# Float_Receiver_PCB.net
KiCad netlist of a schematic drawn in Altium Designer
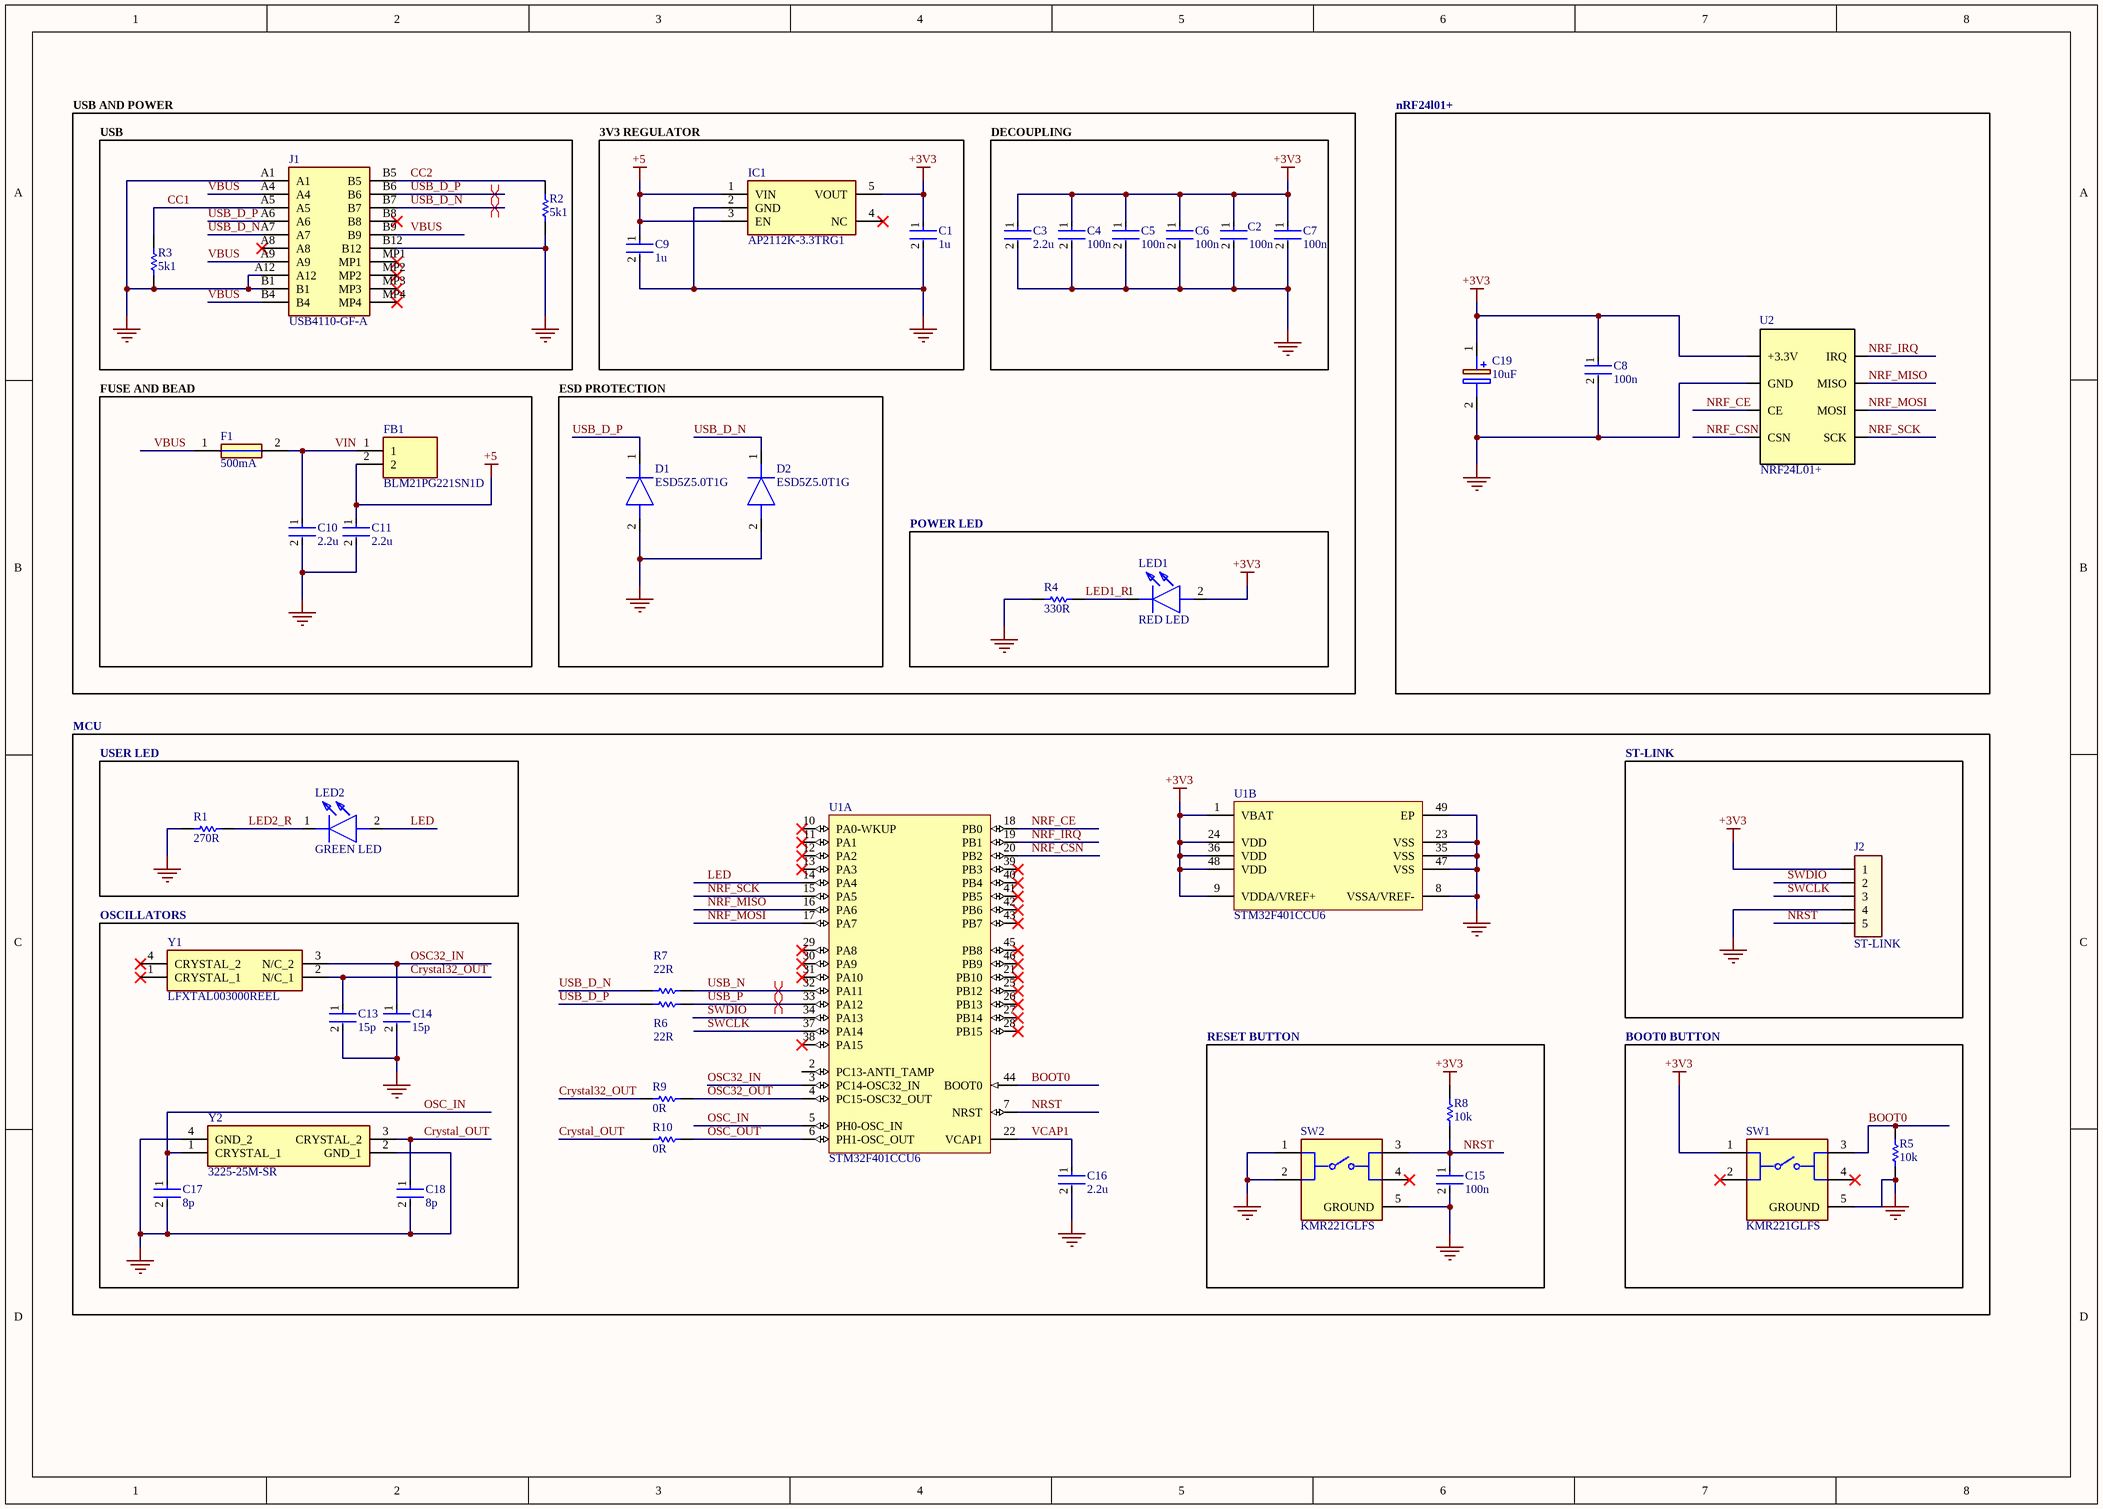
[diagram p0: Float_Receiver_PCB.SchDoc]

(export (version "E")
  (design (tool "Eeschema 10.0.6"))
  (components
    (comp (ref "C1")
      (value "1u")
      (footprint "FP-0805-L_2_01_0_2-W_1_25-MFG")
      (fields (field (name "TOLERANCE") "10%") (field (name "VOLTAGE") "10V"))
      (libsource (lib "Altium Content Vault") (part "b4654b650e69147ec39a6b967a45e02"))
    )
    (comp (ref "C2")
      (value "100n")
      (footprint "FP-0805-L_2_01_0_2-W_1_25-MFG")
      (fields (field (name "TOLERANCE") "10%") (field (name "VOLTAGE") "10V"))
      (libsource (lib "Altium Content Vault") (part "b4654b650e69147ec39a6b967a45e02"))
    )
    (comp (ref "C3")
      (value "2.2u")
      (footprint "FP-0805-L_2_01_0_2-W_1_25-MFG")
      (fields (field (name "TOLERANCE") "10%") (field (name "VOLTAGE") "10V"))
      (libsource (lib "Altium Content Vault") (part "b4654b650e69147ec39a6b967a45e02"))
    )
    (comp (ref "C4")
      (value "100n")
      (footprint "FP-0805-L_2_01_0_2-W_1_25-MFG")
      (fields (field (name "TOLERANCE") "10%") (field (name "VOLTAGE") "10V"))
      (libsource (lib "Altium Content Vault") (part "b4654b650e69147ec39a6b967a45e02"))
    )
    (comp (ref "C5")
      (value "100n")
      (footprint "FP-0805-L_2_01_0_2-W_1_25-MFG")
      (fields (field (name "TOLERANCE") "10%") (field (name "VOLTAGE") "10V"))
      (libsource (lib "Altium Content Vault") (part "b4654b650e69147ec39a6b967a45e02"))
    )
    (comp (ref "C6")
      (value "100n")
      (footprint "FP-0805-L_2_01_0_2-W_1_25-MFG")
      (fields (field (name "TOLERANCE") "10%") (field (name "VOLTAGE") "10V"))
      (libsource (lib "Altium Content Vault") (part "b4654b650e69147ec39a6b967a45e02"))
    )
    (comp (ref "C7")
      (value "100n")
      (footprint "FP-0805-L_2_01_0_2-W_1_25-MFG")
      (fields (field (name "TOLERANCE") "10%") (field (name "VOLTAGE") "10V"))
      (libsource (lib "Altium Content Vault") (part "b4654b650e69147ec39a6b967a45e02"))
    )
    (comp (ref "C8")
      (value "100n")
      (footprint "FP-0805-L_2_01_0_2-W_1_25-MFG")
      (fields (field (name "TOLERANCE") "10%") (field (name "VOLTAGE") "10V"))
      (libsource (lib "Altium Content Vault") (part "b4654b650e69147ec39a6b967a45e02"))
    )
    (comp (ref "C9")
      (value "1u")
      (footprint "FP-0805-L_2_01_0_2-W_1_25-MFG")
      (fields (field (name "TOLERANCE") "10%") (field (name "VOLTAGE") "10V"))
      (libsource (lib "Altium Content Vault") (part "b4654b650e69147ec39a6b967a45e02"))
    )
    (comp (ref "C10")
      (value "2.2u")
      (footprint "FP-0805-L_2_01_0_2-W_1_25-MFG")
      (fields (field (name "TOLERANCE") "10%") (field (name "VOLTAGE") "10V"))
      (libsource (lib "Altium Content Vault") (part "b4654b650e69147ec39a6b967a45e02"))
    )
    (comp (ref "C11")
      (value "2.2u")
      (footprint "FP-0805-L_2_01_0_2-W_1_25-MFG")
      (fields (field (name "TOLERANCE") "10%") (field (name "VOLTAGE") "10V"))
      (libsource (lib "Altium Content Vault") (part "b4654b650e69147ec39a6b967a45e02"))
    )
    (comp (ref "C13")
      (value "15p")
      (footprint "FP-0805-L_2_01_0_2-W_1_25-MFG")
      (fields (field (name "TOLERANCE") "10%") (field (name "VOLTAGE") "10V"))
      (libsource (lib "Altium Content Vault") (part "b4654b650e69147ec39a6b967a45e02"))
    )
    (comp (ref "C14")
      (value "15p")
      (footprint "FP-0805-L_2_01_0_2-W_1_25-MFG")
      (fields (field (name "TOLERANCE") "10%") (field (name "VOLTAGE") "10V"))
      (libsource (lib "Altium Content Vault") (part "b4654b650e69147ec39a6b967a45e02"))
    )
    (comp (ref "C15")
      (value "100n")
      (footprint "FP-0805-L_2_01_0_2-W_1_25-MFG")
      (fields (field (name "TOLERANCE") "10%") (field (name "VOLTAGE") "10V"))
      (libsource (lib "Altium Content Vault") (part "b4654b650e69147ec39a6b967a45e02"))
    )
    (comp (ref "C16")
      (value "2.2u")
      (footprint "FP-0805-L_2_01_0_2-W_1_25-MFG")
      (fields (field (name "TOLERANCE") "10%") (field (name "VOLTAGE") "10V"))
      (libsource (lib "Altium Content Vault") (part "b4654b650e69147ec39a6b967a45e02"))
    )
    (comp (ref "C17")
      (value "8p")
      (footprint "FP-0805-L_2_01_0_2-W_1_25-MFG")
      (fields (field (name "TOLERANCE") "10%") (field (name "VOLTAGE") "10V"))
      (libsource (lib "Altium Content Vault") (part "b4654b650e69147ec39a6b967a45e02"))
    )
    (comp (ref "C18")
      (value "8p")
      (footprint "FP-0805-L_2_01_0_2-W_1_25-MFG")
      (fields (field (name "TOLERANCE") "10%") (field (name "VOLTAGE") "10V"))
      (libsource (lib "Altium Content Vault") (part "b4654b650e69147ec39a6b967a45e02"))
    )
    (comp (ref "C19")
      (value "10uF")
      (footprint "SamacSys:EEE1AA220WR")
      (description "Capacitor Polarised")
      (fields (field (name "MANUFACTURER_PART_NUMBER") "EEE1CA100SR"))
      (libsource (lib "*") (part "EEE1CA100SR"))
    )
    (comp (ref "D1")
      (value "ESD5Z5.0T1G")
      (footprint "SamacSys:SODFL1608X70N")
      (description "Diode")
      (fields (field (name "MOUSER PART NUMBER") "863-ESD5Z5.0T1G"))
      (libsource (lib "*") (part "ESD5Z5.0T1G"))
    )
    (comp (ref "D2")
      (value "ESD5Z5.0T1G")
      (footprint "SamacSys:SODFL1608X70N")
      (description "Diode")
      (fields (field (name "MOUSER PART NUMBER") "863-ESD5Z5.0T1G"))
      (libsource (lib "*") (part "ESD5Z5.0T1G"))
    )
    (comp (ref "F1")
      (value "500mA")
      (footprint "SamacSys:FUSC3216X75N")
      (description "Fuse")
      (fields (field (name "MANUFACTURER_PART_NUMBER") "0ZCJ0025FF2E"))
      (libsource (lib "*") (part "0ZCJ0025FF2E"))
    )
    (comp (ref "FB1")
      (value "BLM21PG221SN1D")
      (footprint "SamacSys:BEADC2012X105N")
      (description "Ferrite Bead")
      (fields (field (name "MOUSER PART NUMBER") "81-BLM21P221SG"))
      (libsource (lib "*") (part "BLM21PG221SN1D"))
    )
    (comp (ref "IC1")
      (value "AP2112K-3.3TRG1")
      (footprint "SamacSys:SOT95P285X140-5N")
      (description "Integrated Circuit")
      (fields (field (name "MOUSER PART NUMBER") "621-AP2112K-3.3TRG1"))
      (libsource (lib "*") (part "AP2112K-3.3TRG1"))
    )
    (comp (ref "J1")
      (value "USB4110-GF-A")
      (footprint "SamacSys:USB4110GFA")
      (description "Connector")
      (fields (field (name "MOUSER PART NUMBER") "640-USB4110-GF-A"))
      (libsource (lib "*") (part "USB4110-GF-A"))
    )
    (comp (ref "J2")
      (value "ST-LINK")
      (footprint "goldpin:goldpin5")
      (libsource (lib "goldpin") (part "goldpin_5"))
    )
    (comp (ref "LED1")
      (value "RED LED")
      (footprint "SamacSys:LEDC2012X80N")
      (description "LED")
      (fields
        (field (name "MANUFACTURER_PART_NUMBER") "HSMG-C170")
        (field (name "MOUSER PART NUMBER") "630-HSMG-C170")
      )
      (libsource (lib "*") (part "HSMG-C170"))
    )
    (comp (ref "LED2")
      (value "GREEN LED")
      (footprint "SamacSys:LEDC2012X80N")
      (description "LED")
      (fields
        (field (name "MANUFACTURER_PART_NUMBER") "HSMG-C170")
        (field (name "MOUSER PART NUMBER") "630-HSMG-C170")
      )
      (libsource (lib "*") (part "HSMG-C170"))
    )
    (comp (ref "R1")
      (value "270R")
      (footprint "RESC2013X60X35ML10T20")
      (fields (field (name "TOLERANCE") "1%") (field (name "MANUFACTURER") "Yageo"))
      (libsource (lib "Altium Content Vault") (part "RES-2"))
    )
    (comp (ref "R2")
      (value "5k1")
      (footprint "RESC2013X60X35ML10T20")
      (fields (field (name "TOLERANCE") "1%") (field (name "MANUFACTURER") "Yageo"))
      (libsource (lib "Altium Content Vault") (part "RES-2"))
    )
    (comp (ref "R3")
      (value "5k1")
      (footprint "RESC2013X60X35ML10T20")
      (fields (field (name "TOLERANCE") "1%") (field (name "MANUFACTURER") "Yageo"))
      (libsource (lib "Altium Content Vault") (part "RES-2"))
    )
    (comp (ref "R4")
      (value "330R")
      (footprint "RESC2013X60X35ML10T20")
      (fields (field (name "TOLERANCE") "1%") (field (name "MANUFACTURER") "Yageo"))
      (libsource (lib "Altium Content Vault") (part "RES-2"))
    )
    (comp (ref "R5")
      (value "10k")
      (footprint "RESC2013X60X35ML10T20")
      (fields (field (name "TOLERANCE") "1%") (field (name "MANUFACTURER") "Yageo"))
      (libsource (lib "Altium Content Vault") (part "RES-2"))
    )
    (comp (ref "R6")
      (value "22R")
      (footprint "RESC2013X60X35ML10T20")
      (fields (field (name "TOLERANCE") "1%") (field (name "MANUFACTURER") "Yageo"))
      (libsource (lib "Altium Content Vault") (part "RES-2"))
    )
    (comp (ref "R7")
      (value "22R")
      (footprint "RESC2013X60X35ML10T20")
      (fields (field (name "TOLERANCE") "1%") (field (name "MANUFACTURER") "Yageo"))
      (libsource (lib "Altium Content Vault") (part "RES-2"))
    )
    (comp (ref "R8")
      (value "10k")
      (footprint "RESC2013X60X35ML10T20")
      (fields (field (name "TOLERANCE") "1%") (field (name "MANUFACTURER") "Yageo"))
      (libsource (lib "Altium Content Vault") (part "RES-2"))
    )
    (comp (ref "R9")
      (value "0R")
      (footprint "RESC2013X60X35ML10T20")
      (fields (field (name "TOLERANCE") "1%") (field (name "MANUFACTURER") "Yageo"))
      (libsource (lib "Altium Content Vault") (part "RES-2"))
    )
    (comp (ref "R10")
      (value "0R")
      (footprint "RESC2013X60X35ML10T20")
      (fields (field (name "TOLERANCE") "1%") (field (name "MANUFACTURER") "Yageo"))
      (libsource (lib "Altium Content Vault") (part "RES-2"))
    )
    (comp (ref "SW1")
      (value "KMR221GLFS")
      (footprint "FP-KMR221GLFS-MFG")
      (description "SWITCH TACTILE SPST-NO 0.05A 32V")
      (libsource (lib "Altium Content Vault") (part "067e1cfe0b8977aedbfee7786663f4c"))
    )
    (comp (ref "SW2")
      (value "KMR221GLFS")
      (footprint "FP-KMR221GLFS-MFG")
      (description "SWITCH TACTILE SPST-NO 0.05A 32V")
      (libsource (lib "Altium Content Vault") (part "067e1cfe0b8977aedbfee7786663f4c"))
    )
    (comp (ref "U1")
      (value "STM32F401CCU6")
      (footprint "STM-UFQFPN48_N")
      (fields (field (name "MANUFACTURER") "STMicroelectronics"))
      (libsource (lib "Altium Content Vault") (part "MC-ARM-STM32F401-SQ48"))
    )
    (comp (ref "U2")
      (value "NRF24L01+ SMD")
      (footprint "PCBComponent_1")
      (libsource (lib "NRF24L01+SMD") (part "NRF24L01+ SMD"))
    )
    (comp (ref "Y1")
      (value "LFXTAL003000REEL")
      (footprint "SamacSys:LFXTAL003000REEL")
      (description "Crystal or Oscillator")
      (fields (field (name "MOUSER PART NUMBER") "449-LFXTAL003000REEL"))
      (libsource (lib "*") (part "LFXTAL003000REEL"))
    )
    (comp (ref "Y2")
      (value "3225-25M-SR")
      (footprint "SamacSys:322525MSR")
      (description "Crystal or Oscillator")
      (libsource (lib "SamacSys") (part "3225-25M-SR"))
    )
  )
  (nets
    (net (code "1") (name "+3V3") (class "Default")
      (node (ref "C1") (pin "1") (pinfunction "1_1") (pintype "passive"))
      (node (ref "C19") (pin "1") (pinfunction "+_1") (pintype "passive"))
      (node (ref "C2") (pin "1") (pinfunction "1_1") (pintype "passive"))
      (node (ref "C3") (pin "1") (pinfunction "1_1") (pintype "passive"))
      (node (ref "C4") (pin "1") (pinfunction "1_1") (pintype "passive"))
      (node (ref "C5") (pin "1") (pinfunction "1_1") (pintype "passive"))
      (node (ref "C6") (pin "1") (pinfunction "1_1") (pintype "passive"))
      (node (ref "C7") (pin "1") (pinfunction "1_1") (pintype "passive"))
      (node (ref "C8") (pin "1") (pinfunction "1_1") (pintype "passive"))
      (node (ref "IC1") (pin "5") (pinfunction "VOUT_5") (pintype "passive"))
      (node (ref "J2") (pin "1") (pinfunction "1_1") (pintype "passive"))
      (node (ref "LED1") (pin "2") (pinfunction "A_2") (pintype "passive"))
      (node (ref "R8") (pin "2") (pinfunction "2_2") (pintype "passive"))
      (node (ref "SW1") (pin "1") (pinfunction "1_1") (pintype "passive"))
      (node (ref "U1") (pin "1") (pinfunction "VBAT_1") (pintype "power_in"))
      (node (ref "U1") (pin "24") (pinfunction "VDD_24") (pintype "power_in"))
      (node (ref "U1") (pin "36") (pinfunction "VDD_36") (pintype "power_in"))
      (node (ref "U1") (pin "48") (pinfunction "VDD_48") (pintype "power_in"))
      (node (ref "U1") (pin "9") (pinfunction "VDDA/VREF+_9") (pintype "power_in"))
      (node (ref "U2") (pin "1") (pinfunction "+3.3V_1") (pintype "passive"))
    )
    (net (code "2") (name "+5") (class "Default")
      (node (ref "C11") (pin "1") (pinfunction "1_1") (pintype "passive"))
      (node (ref "C9") (pin "1") (pinfunction "1_1") (pintype "passive"))
      (node (ref "FB1") (pin "2") (pinfunction "2_2") (pintype "passive"))
      (node (ref "IC1") (pin "1") (pinfunction "VIN_1") (pintype "passive"))
      (node (ref "IC1") (pin "3") (pinfunction "EN_3") (pintype "passive"))
    )
    (net (code "3") (name "/BOOT0") (class "Default")
      (node (ref "R5") (pin "1") (pinfunction "1_1") (pintype "passive"))
      (node (ref "SW1") (pin "3") (pinfunction "3_3") (pintype "passive"))
      (node (ref "U1") (pin "44") (pinfunction "BOOT0_44") (pintype "input"))
    )
    (net (code "4") (name "/CC1") (class "Default")
      (node (ref "J1") (pin "A5") (pinfunction "A5_A5") (pintype "passive"))
      (node (ref "R3") (pin "2") (pinfunction "2_2") (pintype "passive"))
    )
    (net (code "5") (name "/CC2") (class "Default")
      (node (ref "J1") (pin "B5") (pinfunction "B5_B5") (pintype "passive"))
      (node (ref "R2") (pin "2") (pinfunction "2_2") (pintype "passive"))
    )
    (net (code "6") (name "/Crystal32_OUT") (class "Default")
      (node (ref "C13") (pin "1") (pinfunction "1_1") (pintype "passive"))
      (node (ref "R9") (pin "1") (pinfunction "1_1") (pintype "passive"))
      (node (ref "Y1") (pin "2") (pinfunction "N/C_1_2") (pintype "passive"))
    )
    (net (code "7") (name "/Crystal_OUT") (class "Default")
      (node (ref "C18") (pin "1") (pinfunction "1_1") (pintype "passive"))
      (node (ref "R10") (pin "2") (pinfunction "2_2") (pintype "passive"))
      (node (ref "Y2") (pin "3") (pinfunction "CRYSTAL_2_3") (pintype "passive"))
    )
    (net (code "8") (name "/LED") (class "Default")
      (node (ref "LED2") (pin "2") (pinfunction "A_2") (pintype "passive"))
      (node (ref "U1") (pin "14") (pinfunction "PA4_14") (pintype "bidirectional"))
    )
    (net (code "9") (name "/LED1_R") (class "Default")
      (node (ref "LED1") (pin "1") (pinfunction "K_1") (pintype "passive"))
      (node (ref "R4") (pin "2") (pinfunction "2_2") (pintype "passive"))
    )
    (net (code "10") (name "/LED2_R") (class "Default")
      (node (ref "LED2") (pin "1") (pinfunction "K_1") (pintype "passive"))
      (node (ref "R1") (pin "2") (pinfunction "2_2") (pintype "passive"))
    )
    (net (code "11") (name "/NRF_CE") (class "Default")
      (node (ref "U1") (pin "18") (pinfunction "PB0_18") (pintype "bidirectional"))
      (node (ref "U2") (pin "3") (pinfunction "CE_3") (pintype "passive"))
    )
    (net (code "12") (name "/NRF_CSN") (class "Default")
      (node (ref "U1") (pin "20") (pinfunction "PB2_20") (pintype "bidirectional"))
      (node (ref "U2") (pin "4") (pinfunction "CSN_4") (pintype "passive"))
    )
    (net (code "13") (name "/NRF_IRQ") (class "Default")
      (node (ref "U1") (pin "19") (pinfunction "PB1_19") (pintype "bidirectional"))
      (node (ref "U2") (pin "8") (pinfunction "IRQ_8") (pintype "passive"))
    )
    (net (code "14") (name "/NRF_MISO") (class "Default")
      (node (ref "U1") (pin "16") (pinfunction "PA6_16") (pintype "bidirectional"))
      (node (ref "U2") (pin "7") (pinfunction "MISO_7") (pintype "passive"))
    )
    (net (code "15") (name "/NRF_MOSI") (class "Default")
      (node (ref "U1") (pin "17") (pinfunction "PA7_17") (pintype "bidirectional"))
      (node (ref "U2") (pin "6") (pinfunction "MOSI_6") (pintype "passive"))
    )
    (net (code "16") (name "/NRF_SCK") (class "Default")
      (node (ref "U1") (pin "15") (pinfunction "PA5_15") (pintype "bidirectional"))
      (node (ref "U2") (pin "5") (pinfunction "SCK_5") (pintype "passive"))
    )
    (net (code "17") (name "/NRST") (class "Default")
      (node (ref "C15") (pin "1") (pinfunction "1_1") (pintype "passive"))
      (node (ref "J2") (pin "5") (pinfunction "5_5") (pintype "passive"))
      (node (ref "R8") (pin "1") (pinfunction "1_1") (pintype "passive"))
      (node (ref "SW2") (pin "3") (pinfunction "3_3") (pintype "passive"))
      (node (ref "U1") (pin "7") (pinfunction "NRST_7") (pintype "bidirectional"))
    )
    (net (code "18") (name "/OSC32_IN") (class "Default")
      (node (ref "C14") (pin "1") (pinfunction "1_1") (pintype "passive"))
      (node (ref "U1") (pin "3") (pinfunction "PC14-OSC32_IN_3") (pintype "bidirectional"))
      (node (ref "Y1") (pin "3") (pinfunction "N/C_2_3") (pintype "passive"))
    )
    (net (code "19") (name "/OSC32_OUT") (class "Default")
      (node (ref "R9") (pin "2") (pinfunction "2_2") (pintype "passive"))
      (node (ref "U1") (pin "4") (pinfunction "PC15-OSC32_OUT_4") (pintype "bidirectional"))
    )
    (net (code "20") (name "/OSC_IN") (class "Default")
      (node (ref "C17") (pin "1") (pinfunction "1_1") (pintype "passive"))
      (node (ref "U1") (pin "5") (pinfunction "PH0-OSC_IN_5") (pintype "bidirectional"))
      (node (ref "Y2") (pin "1") (pinfunction "CRYSTAL_1_1") (pintype "passive"))
    )
    (net (code "21") (name "/OSC_OUT") (class "Default")
      (node (ref "R10") (pin "1") (pinfunction "1_1") (pintype "passive"))
      (node (ref "U1") (pin "6") (pinfunction "PH1-OSC_OUT_6") (pintype "bidirectional"))
    )
    (net (code "22") (name "/SWCLK") (class "Default")
      (node (ref "J2") (pin "3") (pinfunction "3_3") (pintype "passive"))
      (node (ref "U1") (pin "37") (pinfunction "PA14_37") (pintype "bidirectional"))
    )
    (net (code "23") (name "/SWDIO") (class "Default")
      (node (ref "J2") (pin "2") (pinfunction "2_2") (pintype "passive"))
      (node (ref "U1") (pin "34") (pinfunction "PA13_34") (pintype "bidirectional"))
    )
    (net (code "24") (name "/USB_D_N") (class "Default")
      (node (ref "D2") (pin "1") (pinfunction "K_1") (pintype "passive"))
      (node (ref "J1") (pin "A7") (pinfunction "A7_A7") (pintype "passive"))
      (node (ref "J1") (pin "B7") (pinfunction "B7_B7") (pintype "passive"))
      (node (ref "R7") (pin "2") (pinfunction "2_2") (pintype "passive"))
    )
    (net (code "25") (name "/USB_D_P") (class "Default")
      (node (ref "D1") (pin "1") (pinfunction "K_1") (pintype "passive"))
      (node (ref "J1") (pin "A6") (pinfunction "A6_A6") (pintype "passive"))
      (node (ref "J1") (pin "B6") (pinfunction "B6_B6") (pintype "passive"))
      (node (ref "R6") (pin "2") (pinfunction "2_2") (pintype "passive"))
    )
    (net (code "26") (name "/USB_N") (class "Default")
      (node (ref "R7") (pin "1") (pinfunction "1_1") (pintype "passive"))
      (node (ref "U1") (pin "32") (pinfunction "PA11_32") (pintype "bidirectional"))
    )
    (net (code "27") (name "/USB_P") (class "Default")
      (node (ref "R6") (pin "1") (pinfunction "1_1") (pintype "passive"))
      (node (ref "U1") (pin "33") (pinfunction "PA12_33") (pintype "bidirectional"))
    )
    (net (code "28") (name "/VBUS") (class "Default")
      (node (ref "F1") (pin "1") (pinfunction "1_1") (pintype "passive"))
      (node (ref "J1") (pin "A4") (pinfunction "A4_A4") (pintype "passive"))
      (node (ref "J1") (pin "A9") (pinfunction "A9_A9") (pintype "passive"))
      (node (ref "J1") (pin "B4") (pinfunction "B4_B4") (pintype "passive"))
      (node (ref "J1") (pin "B9") (pinfunction "B9_B9") (pintype "passive"))
    )
    (net (code "29") (name "/VCAP1") (class "Default")
      (node (ref "C16") (pin "1") (pinfunction "1_1") (pintype "passive"))
      (node (ref "U1") (pin "22") (pinfunction "VCAP1_22") (pintype "power_in"))
    )
    (net (code "30") (name "/VIN") (class "Default")
      (node (ref "C10") (pin "1") (pinfunction "1_1") (pintype "passive"))
      (node (ref "F1") (pin "2") (pinfunction "2_2") (pintype "passive"))
      (node (ref "FB1") (pin "1") (pinfunction "1_1") (pintype "passive"))
    )
    (net (code "31") (name "GND") (class "Default")
      (node (ref "C1") (pin "2") (pinfunction "2_2") (pintype "passive"))
      (node (ref "C10") (pin "2") (pinfunction "2_2") (pintype "passive"))
      (node (ref "C11") (pin "2") (pinfunction "2_2") (pintype "passive"))
      (node (ref "C13") (pin "2") (pinfunction "2_2") (pintype "passive"))
      (node (ref "C14") (pin "2") (pinfunction "2_2") (pintype "passive"))
      (node (ref "C15") (pin "2") (pinfunction "2_2") (pintype "passive"))
      (node (ref "C16") (pin "2") (pinfunction "2_2") (pintype "passive"))
      (node (ref "C17") (pin "2") (pinfunction "2_2") (pintype "passive"))
      (node (ref "C18") (pin "2") (pinfunction "2_2") (pintype "passive"))
      (node (ref "C19") (pin "2") (pinfunction "-_2") (pintype "passive"))
      (node (ref "C2") (pin "2") (pinfunction "2_2") (pintype "passive"))
      (node (ref "C3") (pin "2") (pinfunction "2_2") (pintype "passive"))
      (node (ref "C4") (pin "2") (pinfunction "2_2") (pintype "passive"))
      (node (ref "C5") (pin "2") (pinfunction "2_2") (pintype "passive"))
      (node (ref "C6") (pin "2") (pinfunction "2_2") (pintype "passive"))
      (node (ref "C7") (pin "2") (pinfunction "2_2") (pintype "passive"))
      (node (ref "C8") (pin "2") (pinfunction "2_2") (pintype "passive"))
      (node (ref "C9") (pin "2") (pinfunction "2_2") (pintype "passive"))
      (node (ref "D1") (pin "2") (pinfunction "A_2") (pintype "passive"))
      (node (ref "D2") (pin "2") (pinfunction "A_2") (pintype "passive"))
      (node (ref "IC1") (pin "2") (pinfunction "GND_2") (pintype "passive"))
      (node (ref "J1") (pin "A1") (pinfunction "A1_A1") (pintype "passive"))
      (node (ref "J1") (pin "A12") (pinfunction "A12_A12") (pintype "passive"))
      (node (ref "J1") (pin "B1") (pinfunction "B1_B1") (pintype "passive"))
      (node (ref "J1") (pin "B12") (pinfunction "B12_B12") (pintype "passive"))
      (node (ref "J2") (pin "4") (pinfunction "4_4") (pintype "passive"))
      (node (ref "R1") (pin "1") (pinfunction "1_1") (pintype "passive"))
      (node (ref "R2") (pin "1") (pinfunction "1_1") (pintype "passive"))
      (node (ref "R3") (pin "1") (pinfunction "1_1") (pintype "passive"))
      (node (ref "R4") (pin "1") (pinfunction "1_1") (pintype "passive"))
      (node (ref "R5") (pin "2") (pinfunction "2_2") (pintype "passive"))
      (node (ref "SW1") (pin "5") (pinfunction "GROUND_5") (pintype "power_in"))
      (node (ref "SW2") (pin "1") (pinfunction "1_1") (pintype "passive"))
      (node (ref "SW2") (pin "2") (pinfunction "2_2") (pintype "passive"))
      (node (ref "SW2") (pin "5") (pinfunction "GROUND_5") (pintype "power_in"))
      (node (ref "U1") (pin "23") (pinfunction "VSS_23") (pintype "power_in"))
      (node (ref "U1") (pin "35") (pinfunction "VSS_35") (pintype "power_in"))
      (node (ref "U1") (pin "47") (pinfunction "VSS_47") (pintype "power_in"))
      (node (ref "U1") (pin "49") (pinfunction "EP_49") (pintype "power_in"))
      (node (ref "U1") (pin "8") (pinfunction "VSSA/VREF-_8") (pintype "power_in"))
      (node (ref "U2") (pin "2") (pinfunction "GND_2") (pintype "passive"))
      (node (ref "Y2") (pin "2") (pinfunction "GND_1_2") (pintype "passive"))
      (node (ref "Y2") (pin "4") (pinfunction "GND_2_4") (pintype "passive"))
    )
    (net (code "32") (name "unconnected-(IC1-NC-Pad4)") (class "Default")
      (node (ref "IC1") (pin "4") (pinfunction "NC_4") (pintype "passive+no_connect"))
    )
    (net (code "33") (name "unconnected-(J1-PadA8)") (class "Default")
      (node (ref "J1") (pin "A8") (pinfunction "A8_A8") (pintype "passive+no_connect"))
    )
    (net (code "34") (name "unconnected-(J1-PadB8)") (class "Default")
      (node (ref "J1") (pin "B8") (pinfunction "B8_B8") (pintype "passive+no_connect"))
    )
    (net (code "35") (name "unconnected-(J1-PadMP1)") (class "Default")
      (node (ref "J1") (pin "MP1") (pinfunction "MP1_MP1") (pintype "passive+no_connect"))
    )
    (net (code "36") (name "unconnected-(J1-PadMP2)") (class "Default")
      (node (ref "J1") (pin "MP2") (pinfunction "MP2_MP2") (pintype "passive+no_connect"))
    )
    (net (code "37") (name "unconnected-(J1-PadMP3)") (class "Default")
      (node (ref "J1") (pin "MP3") (pinfunction "MP3_MP3") (pintype "passive+no_connect"))
    )
    (net (code "38") (name "unconnected-(J1-PadMP4)") (class "Default")
      (node (ref "J1") (pin "MP4") (pinfunction "MP4_MP4") (pintype "passive+no_connect"))
    )
    (net (code "39") (name "unconnected-(SW1-Pad2)") (class "Default")
      (node (ref "SW1") (pin "2") (pinfunction "2_2") (pintype "passive+no_connect"))
    )
    (net (code "40") (name "unconnected-(SW1-Pad4)") (class "Default")
      (node (ref "SW1") (pin "4") (pinfunction "4_4") (pintype "passive+no_connect"))
    )
    (net (code "41") (name "unconnected-(SW2-Pad4)") (class "Default")
      (node (ref "SW2") (pin "4") (pinfunction "4_4") (pintype "passive+no_connect"))
    )
    (net (code "42") (name "unconnected-(U1A-PA0-WKUP-Pad10)") (class "Default")
      (node (ref "U1") (pin "10") (pinfunction "PA0-WKUP_10") (pintype "bidirectional+no_connect"))
    )
    (net (code "43") (name "unconnected-(U1A-PA1-Pad11)") (class "Default")
      (node (ref "U1") (pin "11") (pinfunction "PA1_11") (pintype "bidirectional+no_connect"))
    )
    (net (code "44") (name "unconnected-(U1A-PA2-Pad12)") (class "Default")
      (node (ref "U1") (pin "12") (pinfunction "PA2_12") (pintype "bidirectional+no_connect"))
    )
    (net (code "45") (name "unconnected-(U1A-PA3-Pad13)") (class "Default")
      (node (ref "U1") (pin "13") (pinfunction "PA3_13") (pintype "bidirectional+no_connect"))
    )
    (net (code "46") (name "unconnected-(U1A-PA8-Pad29)") (class "Default")
      (node (ref "U1") (pin "29") (pinfunction "PA8_29") (pintype "bidirectional+no_connect"))
    )
    (net (code "47") (name "unconnected-(U1A-PA9-Pad30)") (class "Default")
      (node (ref "U1") (pin "30") (pinfunction "PA9_30") (pintype "bidirectional+no_connect"))
    )
    (net (code "48") (name "unconnected-(U1A-PA10-Pad31)") (class "Default")
      (node (ref "U1") (pin "31") (pinfunction "PA10_31") (pintype "bidirectional+no_connect"))
    )
    (net (code "49") (name "unconnected-(U1A-PA15-Pad38)") (class "Default")
      (node (ref "U1") (pin "38") (pinfunction "PA15_38") (pintype "bidirectional+no_connect"))
    )
    (net (code "50") (name "unconnected-(U1A-PB3-Pad39)") (class "Default")
      (node (ref "U1") (pin "39") (pinfunction "PB3_39") (pintype "bidirectional+no_connect"))
    )
    (net (code "51") (name "unconnected-(U1A-PB4-Pad40)") (class "Default")
      (node (ref "U1") (pin "40") (pinfunction "PB4_40") (pintype "bidirectional+no_connect"))
    )
    (net (code "52") (name "unconnected-(U1A-PB5-Pad41)") (class "Default")
      (node (ref "U1") (pin "41") (pinfunction "PB5_41") (pintype "bidirectional+no_connect"))
    )
    (net (code "53") (name "unconnected-(U1A-PB6-Pad42)") (class "Default")
      (node (ref "U1") (pin "42") (pinfunction "PB6_42") (pintype "bidirectional+no_connect"))
    )
    (net (code "54") (name "unconnected-(U1A-PB7-Pad43)") (class "Default")
      (node (ref "U1") (pin "43") (pinfunction "PB7_43") (pintype "bidirectional+no_connect"))
    )
    (net (code "55") (name "unconnected-(U1A-PB8-Pad45)") (class "Default")
      (node (ref "U1") (pin "45") (pinfunction "PB8_45") (pintype "bidirectional+no_connect"))
    )
    (net (code "56") (name "unconnected-(U1A-PB9-Pad46)") (class "Default")
      (node (ref "U1") (pin "46") (pinfunction "PB9_46") (pintype "bidirectional+no_connect"))
    )
    (net (code "57") (name "unconnected-(U1A-PB10-Pad21)") (class "Default")
      (node (ref "U1") (pin "21") (pinfunction "PB10_21") (pintype "bidirectional+no_connect"))
    )
    (net (code "58") (name "unconnected-(U1A-PB12-Pad25)") (class "Default")
      (node (ref "U1") (pin "25") (pinfunction "PB12_25") (pintype "bidirectional+no_connect"))
    )
    (net (code "59") (name "unconnected-(U1A-PB13-Pad26)") (class "Default")
      (node (ref "U1") (pin "26") (pinfunction "PB13_26") (pintype "bidirectional+no_connect"))
    )
    (net (code "60") (name "unconnected-(U1A-PB14-Pad27)") (class "Default")
      (node (ref "U1") (pin "27") (pinfunction "PB14_27") (pintype "bidirectional+no_connect"))
    )
    (net (code "61") (name "unconnected-(U1A-PB15-Pad28)") (class "Default")
      (node (ref "U1") (pin "28") (pinfunction "PB15_28") (pintype "bidirectional+no_connect"))
    )
    (net (code "62") (name "unconnected-(U1A-PC13-ANTI_TAMP-Pad2)") (class "Default")
      (node (ref "U1") (pin "2") (pinfunction "PC13-ANTI_TAMP_2") (pintype "bidirectional"))
    )
    (net (code "63") (name "unconnected-(Y1-CRYSTAL_1-Pad1)") (class "Default")
      (node (ref "Y1") (pin "1") (pinfunction "CRYSTAL_1_1") (pintype "passive+no_connect"))
    )
    (net (code "64") (name "unconnected-(Y1-CRYSTAL_2-Pad4)") (class "Default")
      (node (ref "Y1") (pin "4") (pinfunction "CRYSTAL_2_4") (pintype "passive+no_connect"))
    )
  )
)
